# inversor.net
KiCad netlist of a schematic drawn in EAGLE
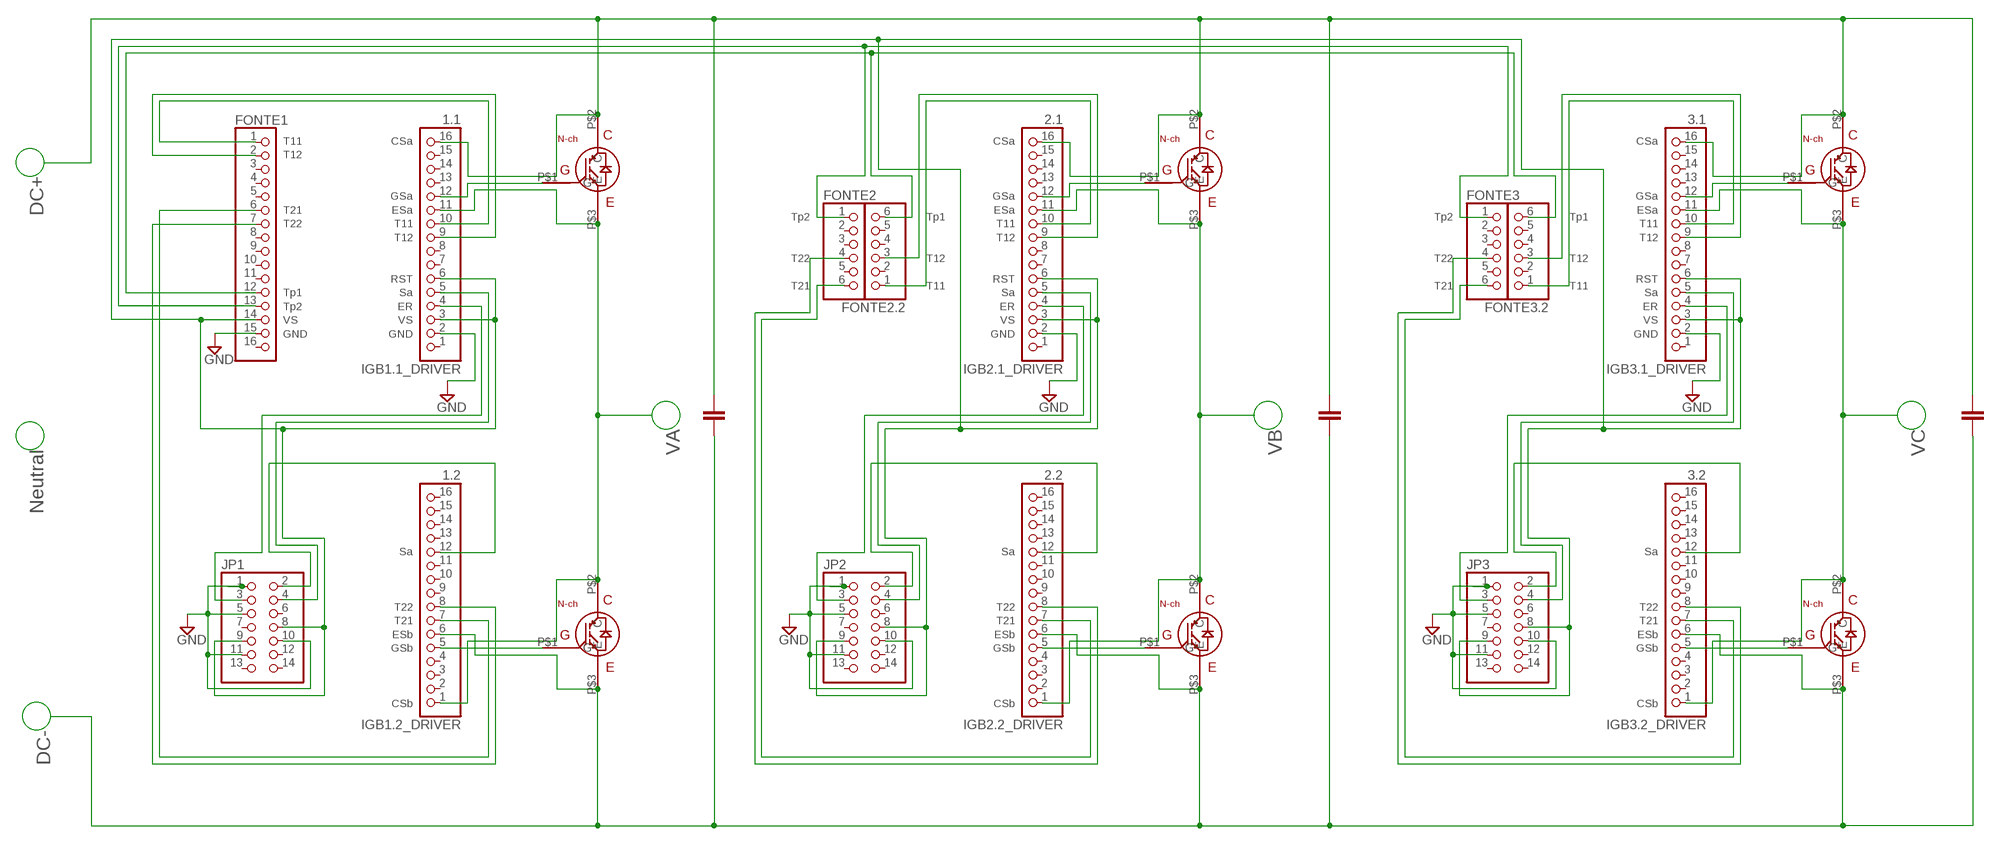
[diagram p0: schematic, sheet 1]

(export (version "E")
  (design (tool "Eeschema 10.0.6"))
  (components
    (comp (ref "FONTE1")
      (value "PINHD-1X16")
      (footprint "eagle-import:1X16")
      (libsource (lib "eagle-import") (part "PINHD-1X16"))
    )
    (comp (ref "FONTE2")
      (value "PINHD-1X6")
      (footprint "eagle-import:1X06")
      (libsource (lib "eagle-import") (part "PINHD-1X6"))
    )
    (comp (ref "FONTE2.2")
      (value "PINHD-1X6")
      (footprint "eagle-import:1X06")
      (libsource (lib "eagle-import") (part "PINHD-1X6"))
    )
    (comp (ref "FONTE3")
      (value "PINHD-1X6")
      (footprint "eagle-import:1X06")
      (libsource (lib "eagle-import") (part "PINHD-1X6"))
    )
    (comp (ref "FONTE3.2")
      (value "PINHD-1X6")
      (footprint "eagle-import:1X06")
      (libsource (lib "eagle-import") (part "PINHD-1X6"))
    )
    (comp (ref "IGB1.1_DRIVER")
      (value "1.1")
      (footprint "eagle-import:1X16")
      (libsource (lib "eagle-import") (part "PINHD-1X16"))
    )
    (comp (ref "IGB1.2_DRIVER")
      (value "1.2")
      (footprint "eagle-import:1X16")
      (libsource (lib "eagle-import") (part "PINHD-1X16"))
    )
    (comp (ref "IGB2.1_DRIVER")
      (value "2.1")
      (footprint "eagle-import:1X16")
      (libsource (lib "eagle-import") (part "PINHD-1X16"))
    )
    (comp (ref "IGB2.2_DRIVER")
      (value "2.2")
      (footprint "eagle-import:1X16")
      (libsource (lib "eagle-import") (part "PINHD-1X16"))
    )
    (comp (ref "IGB3.1_DRIVER")
      (value "3.1")
      (footprint "eagle-import:1X16")
      (libsource (lib "eagle-import") (part "PINHD-1X16"))
    )
    (comp (ref "IGB3.2_DRIVER")
      (value "3.2")
      (footprint "eagle-import:1X16")
      (libsource (lib "eagle-import") (part "PINHD-1X16"))
    )
    (comp (ref "JP1")
      (value "PINHD-2X7")
      (footprint "eagle-import:2X07")
      (libsource (lib "eagle-import") (part "PINHD-2X7"))
    )
    (comp (ref "JP2")
      (value "PINHD-2X7")
      (footprint "eagle-import:2X07")
      (libsource (lib "eagle-import") (part "PINHD-2X7"))
    )
    (comp (ref "JP3")
      (value "PINHD-2X7")
      (footprint "eagle-import:2X07")
      (libsource (lib "eagle-import") (part "PINHD-2X7"))
    )
    (comp (ref "U$1")
      (value "TO-247A")
      (footprint "eagle-import:TO-247")
      (libsource (lib "eagle-import") (part "TO-247A"))
    )
    (comp (ref "U$2")
      (value "TO-247A")
      (footprint "eagle-import:TO-247")
      (libsource (lib "eagle-import") (part "TO-247A"))
    )
    (comp (ref "U$3")
      (value "TO-247A")
      (footprint "eagle-import:TO-247")
      (libsource (lib "eagle-import") (part "TO-247A"))
    )
    (comp (ref "U$4")
      (value "TO-247A")
      (footprint "eagle-import:TO-247")
      (libsource (lib "eagle-import") (part "TO-247A"))
    )
    (comp (ref "U$5")
      (value "TO-247A")
      (footprint "eagle-import:TO-247")
      (libsource (lib "eagle-import") (part "TO-247A"))
    )
    (comp (ref "U$6")
      (value "TO-247A")
      (footprint "eagle-import:TO-247")
      (libsource (lib "eagle-import") (part "TO-247A"))
    )
  )
  (nets
    (net (code "1") (name "GND") (class "Default")
      (node (ref "FONTE1") (pin "15") (pinfunction "15_15") (pintype "passive"))
      (node (ref "IGB1.1_DRIVER") (pin "2") (pinfunction "2_2") (pintype "passive"))
      (node (ref "IGB2.1_DRIVER") (pin "2") (pinfunction "2_2") (pintype "passive"))
      (node (ref "IGB3.1_DRIVER") (pin "2") (pinfunction "2_2") (pintype "passive"))
      (node (ref "JP1") (pin "1") (pinfunction "1_1") (pintype "passive"))
      (node (ref "JP1") (pin "10") (pinfunction "10_10") (pintype "passive"))
      (node (ref "JP1") (pin "11") (pinfunction "11_11") (pintype "passive"))
      (node (ref "JP1") (pin "5") (pinfunction "5_5") (pintype "passive"))
      (node (ref "JP2") (pin "1") (pinfunction "1_1") (pintype "passive"))
      (node (ref "JP2") (pin "10") (pinfunction "10_10") (pintype "passive"))
      (node (ref "JP2") (pin "11") (pinfunction "11_11") (pintype "passive"))
      (node (ref "JP2") (pin "5") (pinfunction "5_5") (pintype "passive"))
      (node (ref "JP3") (pin "1") (pinfunction "1_1") (pintype "passive"))
      (node (ref "JP3") (pin "10") (pinfunction "10_10") (pintype "passive"))
      (node (ref "JP3") (pin "11") (pinfunction "11_11") (pintype "passive"))
      (node (ref "JP3") (pin "5") (pinfunction "5_5") (pintype "passive"))
    )
    (net (code "2") (name "Net-(FONTE1-Pad1)") (class "Default")
      (node (ref "FONTE1") (pin "1") (pinfunction "1_1") (pintype "passive"))
      (node (ref "IGB1.1_DRIVER") (pin "10") (pinfunction "10_10") (pintype "passive"))
    )
    (net (code "3") (name "Net-(FONTE1-Pad2)") (class "Default")
      (node (ref "FONTE1") (pin "2") (pinfunction "2_2") (pintype "passive"))
      (node (ref "IGB1.1_DRIVER") (pin "9") (pinfunction "9_9") (pintype "passive"))
    )
    (net (code "4") (name "Net-(FONTE1-Pad6)") (class "Default")
      (node (ref "FONTE1") (pin "6") (pinfunction "6_6") (pintype "passive"))
      (node (ref "IGB1.2_DRIVER") (pin "7") (pinfunction "7_7") (pintype "passive"))
    )
    (net (code "5") (name "Net-(FONTE1-Pad7)") (class "Default")
      (node (ref "FONTE1") (pin "7") (pinfunction "7_7") (pintype "passive"))
      (node (ref "IGB1.2_DRIVER") (pin "8") (pinfunction "8_8") (pintype "passive"))
    )
    (net (code "6") (name "Net-(FONTE1-Pad12)") (class "Default")
      (node (ref "FONTE1") (pin "12") (pinfunction "12_12") (pintype "passive"))
      (node (ref "FONTE2.2") (pin "6") (pinfunction "6_6") (pintype "passive"))
      (node (ref "FONTE3.2") (pin "6") (pinfunction "6_6") (pintype "passive"))
    )
    (net (code "7") (name "Net-(FONTE1-Pad13)") (class "Default")
      (node (ref "FONTE1") (pin "13") (pinfunction "13_13") (pintype "passive"))
      (node (ref "FONTE2") (pin "1") (pinfunction "1_1") (pintype "passive"))
      (node (ref "FONTE3") (pin "1") (pinfunction "1_1") (pintype "passive"))
    )
    (net (code "8") (name "Net-(FONTE1-Pad14)") (class "Default")
      (node (ref "FONTE1") (pin "14") (pinfunction "14_14") (pintype "passive"))
      (node (ref "IGB1.1_DRIVER") (pin "3") (pinfunction "3_3") (pintype "passive"))
      (node (ref "IGB1.1_DRIVER") (pin "6") (pinfunction "6_6") (pintype "passive"))
      (node (ref "IGB2.1_DRIVER") (pin "3") (pinfunction "3_3") (pintype "passive"))
      (node (ref "IGB2.1_DRIVER") (pin "6") (pinfunction "6_6") (pintype "passive"))
      (node (ref "IGB3.1_DRIVER") (pin "3") (pinfunction "3_3") (pintype "passive"))
      (node (ref "IGB3.1_DRIVER") (pin "6") (pinfunction "6_6") (pintype "passive"))
      (node (ref "JP1") (pin "8") (pinfunction "8_8") (pintype "passive"))
      (node (ref "JP1") (pin "9") (pinfunction "9_9") (pintype "passive"))
      (node (ref "JP2") (pin "8") (pinfunction "8_8") (pintype "passive"))
      (node (ref "JP2") (pin "9") (pinfunction "9_9") (pintype "passive"))
      (node (ref "JP3") (pin "8") (pinfunction "8_8") (pintype "passive"))
      (node (ref "JP3") (pin "9") (pinfunction "9_9") (pintype "passive"))
    )
    (net (code "9") (name "Net-(FONTE2-Pad4)") (class "Default")
      (node (ref "FONTE2") (pin "4") (pinfunction "4_4") (pintype "passive"))
      (node (ref "IGB2.2_DRIVER") (pin "8") (pinfunction "8_8") (pintype "passive"))
    )
    (net (code "10") (name "Net-(FONTE2-Pad6)") (class "Default")
      (node (ref "FONTE2") (pin "6") (pinfunction "6_6") (pintype "passive"))
      (node (ref "IGB2.2_DRIVER") (pin "7") (pinfunction "7_7") (pintype "passive"))
    )
    (net (code "11") (name "Net-(FONTE2.2-Pad1)") (class "Default")
      (node (ref "FONTE2.2") (pin "1") (pinfunction "1_1") (pintype "passive"))
      (node (ref "IGB2.1_DRIVER") (pin "10") (pinfunction "10_10") (pintype "passive"))
    )
    (net (code "12") (name "Net-(FONTE2.2-Pad3)") (class "Default")
      (node (ref "FONTE2.2") (pin "3") (pinfunction "3_3") (pintype "passive"))
      (node (ref "IGB2.1_DRIVER") (pin "9") (pinfunction "9_9") (pintype "passive"))
    )
    (net (code "13") (name "Net-(FONTE3-Pad4)") (class "Default")
      (node (ref "FONTE3") (pin "4") (pinfunction "4_4") (pintype "passive"))
      (node (ref "IGB3.2_DRIVER") (pin "8") (pinfunction "8_8") (pintype "passive"))
    )
    (net (code "14") (name "Net-(FONTE3-Pad6)") (class "Default")
      (node (ref "FONTE3") (pin "6") (pinfunction "6_6") (pintype "passive"))
      (node (ref "IGB3.2_DRIVER") (pin "7") (pinfunction "7_7") (pintype "passive"))
    )
    (net (code "15") (name "Net-(FONTE3.2-Pad1)") (class "Default")
      (node (ref "FONTE3.2") (pin "1") (pinfunction "1_1") (pintype "passive"))
      (node (ref "IGB3.1_DRIVER") (pin "10") (pinfunction "10_10") (pintype "passive"))
    )
    (net (code "16") (name "Net-(FONTE3.2-Pad3)") (class "Default")
      (node (ref "FONTE3.2") (pin "3") (pinfunction "3_3") (pintype "passive"))
      (node (ref "IGB3.1_DRIVER") (pin "9") (pinfunction "9_9") (pintype "passive"))
    )
    (net (code "17") (name "Net-(IGB1.1_DRIVER-Pad4)") (class "Default")
      (node (ref "IGB1.1_DRIVER") (pin "4") (pinfunction "4_4") (pintype "passive"))
      (node (ref "JP1") (pin "3") (pinfunction "3_3") (pintype "passive"))
    )
    (net (code "18") (name "Net-(IGB1.1_DRIVER-Pad5)") (class "Default")
      (node (ref "IGB1.1_DRIVER") (pin "5") (pinfunction "5_5") (pintype "passive"))
      (node (ref "JP1") (pin "4") (pinfunction "4_4") (pintype "passive"))
    )
    (net (code "19") (name "Net-(IGB1.2_DRIVER-Pad12)") (class "Default")
      (node (ref "IGB1.2_DRIVER") (pin "12") (pinfunction "12_12") (pintype "passive"))
      (node (ref "JP1") (pin "2") (pinfunction "2_2") (pintype "passive"))
    )
    (net (code "20") (name "Net-(IGB2.1_DRIVER-Pad4)") (class "Default")
      (node (ref "IGB2.1_DRIVER") (pin "4") (pinfunction "4_4") (pintype "passive"))
      (node (ref "JP2") (pin "3") (pinfunction "3_3") (pintype "passive"))
    )
    (net (code "21") (name "Net-(IGB2.1_DRIVER-Pad5)") (class "Default")
      (node (ref "IGB2.1_DRIVER") (pin "5") (pinfunction "5_5") (pintype "passive"))
      (node (ref "JP2") (pin "4") (pinfunction "4_4") (pintype "passive"))
    )
    (net (code "22") (name "Net-(IGB2.2_DRIVER-Pad12)") (class "Default")
      (node (ref "IGB2.2_DRIVER") (pin "12") (pinfunction "12_12") (pintype "passive"))
      (node (ref "JP2") (pin "2") (pinfunction "2_2") (pintype "passive"))
    )
    (net (code "23") (name "Net-(IGB3.1_DRIVER-Pad4)") (class "Default")
      (node (ref "IGB3.1_DRIVER") (pin "4") (pinfunction "4_4") (pintype "passive"))
      (node (ref "JP3") (pin "3") (pinfunction "3_3") (pintype "passive"))
    )
    (net (code "24") (name "Net-(IGB3.1_DRIVER-Pad5)") (class "Default")
      (node (ref "IGB3.1_DRIVER") (pin "5") (pinfunction "5_5") (pintype "passive"))
      (node (ref "JP3") (pin "4") (pinfunction "4_4") (pintype "passive"))
    )
    (net (code "25") (name "Net-(IGB3.2_DRIVER-Pad12)") (class "Default")
      (node (ref "IGB3.2_DRIVER") (pin "12") (pinfunction "12_12") (pintype "passive"))
      (node (ref "JP3") (pin "2") (pinfunction "2_2") (pintype "passive"))
    )
    (net (code "26") (name "Net-(U$1-C)") (class "Default")
      (node (ref "IGB1.1_DRIVER") (pin "16") (pinfunction "16_16") (pintype "passive"))
      (node (ref "IGB2.1_DRIVER") (pin "16") (pinfunction "16_16") (pintype "passive"))
      (node (ref "IGB3.1_DRIVER") (pin "16") (pinfunction "16_16") (pintype "passive"))
      (node (ref "U$1") (pin "P$2") (pinfunction "C_P$2") (pintype "bidirectional"))
      (node (ref "U$3") (pin "P$2") (pinfunction "C_P$2") (pintype "bidirectional"))
      (node (ref "U$5") (pin "P$2") (pinfunction "C_P$2") (pintype "bidirectional"))
    )
    (net (code "27") (name "Net-(U$1-E)") (class "Default")
      (node (ref "IGB1.1_DRIVER") (pin "11") (pinfunction "11_11") (pintype "passive"))
      (node (ref "IGB1.2_DRIVER") (pin "1") (pinfunction "1_1") (pintype "passive"))
      (node (ref "U$1") (pin "P$3") (pinfunction "E_P$3") (pintype "bidirectional"))
      (node (ref "U$2") (pin "P$2") (pinfunction "C_P$2") (pintype "bidirectional"))
    )
    (net (code "28") (name "Net-(U$1-G)") (class "Default")
      (node (ref "IGB1.1_DRIVER") (pin "12") (pinfunction "12_12") (pintype "passive"))
      (node (ref "U$1") (pin "P$1") (pinfunction "G_P$1") (pintype "bidirectional"))
    )
    (net (code "29") (name "Net-(U$2-E)") (class "Default")
      (node (ref "IGB1.2_DRIVER") (pin "6") (pinfunction "6_6") (pintype "passive"))
      (node (ref "IGB2.2_DRIVER") (pin "6") (pinfunction "6_6") (pintype "passive"))
      (node (ref "IGB3.2_DRIVER") (pin "6") (pinfunction "6_6") (pintype "passive"))
      (node (ref "U$2") (pin "P$3") (pinfunction "E_P$3") (pintype "bidirectional"))
      (node (ref "U$4") (pin "P$3") (pinfunction "E_P$3") (pintype "bidirectional"))
      (node (ref "U$6") (pin "P$3") (pinfunction "E_P$3") (pintype "bidirectional"))
    )
    (net (code "30") (name "Net-(U$2-G)") (class "Default")
      (node (ref "IGB1.2_DRIVER") (pin "5") (pinfunction "5_5") (pintype "passive"))
      (node (ref "U$2") (pin "P$1") (pinfunction "G_P$1") (pintype "bidirectional"))
    )
    (net (code "31") (name "Net-(U$3-E)") (class "Default")
      (node (ref "IGB2.1_DRIVER") (pin "11") (pinfunction "11_11") (pintype "passive"))
      (node (ref "IGB2.2_DRIVER") (pin "1") (pinfunction "1_1") (pintype "passive"))
      (node (ref "U$3") (pin "P$3") (pinfunction "E_P$3") (pintype "bidirectional"))
      (node (ref "U$4") (pin "P$2") (pinfunction "C_P$2") (pintype "bidirectional"))
    )
    (net (code "32") (name "Net-(U$3-G)") (class "Default")
      (node (ref "IGB2.1_DRIVER") (pin "12") (pinfunction "12_12") (pintype "passive"))
      (node (ref "U$3") (pin "P$1") (pinfunction "G_P$1") (pintype "bidirectional"))
    )
    (net (code "33") (name "Net-(U$4-G)") (class "Default")
      (node (ref "IGB2.2_DRIVER") (pin "5") (pinfunction "5_5") (pintype "passive"))
      (node (ref "U$4") (pin "P$1") (pinfunction "G_P$1") (pintype "bidirectional"))
    )
    (net (code "34") (name "Net-(U$5-E)") (class "Default")
      (node (ref "IGB3.1_DRIVER") (pin "11") (pinfunction "11_11") (pintype "passive"))
      (node (ref "IGB3.2_DRIVER") (pin "1") (pinfunction "1_1") (pintype "passive"))
      (node (ref "U$5") (pin "P$3") (pinfunction "E_P$3") (pintype "bidirectional"))
      (node (ref "U$6") (pin "P$2") (pinfunction "C_P$2") (pintype "bidirectional"))
    )
    (net (code "35") (name "Net-(U$5-G)") (class "Default")
      (node (ref "IGB3.1_DRIVER") (pin "12") (pinfunction "12_12") (pintype "passive"))
      (node (ref "U$5") (pin "P$1") (pinfunction "G_P$1") (pintype "bidirectional"))
    )
    (net (code "36") (name "Net-(U$6-G)") (class "Default")
      (node (ref "IGB3.2_DRIVER") (pin "5") (pinfunction "5_5") (pintype "passive"))
      (node (ref "U$6") (pin "P$1") (pinfunction "G_P$1") (pintype "bidirectional"))
    )
    (net (code "37") (name "unconnected-(FONTE1-Pad3)") (class "Default")
      (node (ref "FONTE1") (pin "3") (pinfunction "3_3") (pintype "passive"))
    )
    (net (code "38") (name "unconnected-(FONTE1-Pad4)") (class "Default")
      (node (ref "FONTE1") (pin "4") (pinfunction "4_4") (pintype "passive"))
    )
    (net (code "39") (name "unconnected-(FONTE1-Pad5)") (class "Default")
      (node (ref "FONTE1") (pin "5") (pinfunction "5_5") (pintype "passive"))
    )
    (net (code "40") (name "unconnected-(FONTE1-Pad8)") (class "Default")
      (node (ref "FONTE1") (pin "8") (pinfunction "8_8") (pintype "passive"))
    )
    (net (code "41") (name "unconnected-(FONTE1-Pad9)") (class "Default")
      (node (ref "FONTE1") (pin "9") (pinfunction "9_9") (pintype "passive"))
    )
    (net (code "42") (name "unconnected-(FONTE1-Pad10)") (class "Default")
      (node (ref "FONTE1") (pin "10") (pinfunction "10_10") (pintype "passive"))
    )
    (net (code "43") (name "unconnected-(FONTE1-Pad11)") (class "Default")
      (node (ref "FONTE1") (pin "11") (pinfunction "11_11") (pintype "passive"))
    )
    (net (code "44") (name "unconnected-(FONTE1-Pad16)") (class "Default")
      (node (ref "FONTE1") (pin "16") (pinfunction "16_16") (pintype "passive"))
    )
    (net (code "45") (name "unconnected-(FONTE2-Pad2)") (class "Default")
      (node (ref "FONTE2") (pin "2") (pinfunction "2_2") (pintype "passive"))
    )
    (net (code "46") (name "unconnected-(FONTE2-Pad3)") (class "Default")
      (node (ref "FONTE2") (pin "3") (pinfunction "3_3") (pintype "passive"))
    )
    (net (code "47") (name "unconnected-(FONTE2-Pad5)") (class "Default")
      (node (ref "FONTE2") (pin "5") (pinfunction "5_5") (pintype "passive"))
    )
    (net (code "48") (name "unconnected-(FONTE2.2-Pad2)") (class "Default")
      (node (ref "FONTE2.2") (pin "2") (pinfunction "2_2") (pintype "passive"))
    )
    (net (code "49") (name "unconnected-(FONTE2.2-Pad4)") (class "Default")
      (node (ref "FONTE2.2") (pin "4") (pinfunction "4_4") (pintype "passive"))
    )
    (net (code "50") (name "unconnected-(FONTE2.2-Pad5)") (class "Default")
      (node (ref "FONTE2.2") (pin "5") (pinfunction "5_5") (pintype "passive"))
    )
    (net (code "51") (name "unconnected-(FONTE3-Pad2)") (class "Default")
      (node (ref "FONTE3") (pin "2") (pinfunction "2_2") (pintype "passive"))
    )
    (net (code "52") (name "unconnected-(FONTE3-Pad3)") (class "Default")
      (node (ref "FONTE3") (pin "3") (pinfunction "3_3") (pintype "passive"))
    )
    (net (code "53") (name "unconnected-(FONTE3-Pad5)") (class "Default")
      (node (ref "FONTE3") (pin "5") (pinfunction "5_5") (pintype "passive"))
    )
    (net (code "54") (name "unconnected-(FONTE3.2-Pad2)") (class "Default")
      (node (ref "FONTE3.2") (pin "2") (pinfunction "2_2") (pintype "passive"))
    )
    (net (code "55") (name "unconnected-(FONTE3.2-Pad4)") (class "Default")
      (node (ref "FONTE3.2") (pin "4") (pinfunction "4_4") (pintype "passive"))
    )
    (net (code "56") (name "unconnected-(FONTE3.2-Pad5)") (class "Default")
      (node (ref "FONTE3.2") (pin "5") (pinfunction "5_5") (pintype "passive"))
    )
    (net (code "57") (name "unconnected-(IGB1.1_DRIVER-Pad1)") (class "Default")
      (node (ref "IGB1.1_DRIVER") (pin "1") (pinfunction "1_1") (pintype "passive"))
    )
    (net (code "58") (name "unconnected-(IGB1.1_DRIVER-Pad7)") (class "Default")
      (node (ref "IGB1.1_DRIVER") (pin "7") (pinfunction "7_7") (pintype "passive"))
    )
    (net (code "59") (name "unconnected-(IGB1.1_DRIVER-Pad8)") (class "Default")
      (node (ref "IGB1.1_DRIVER") (pin "8") (pinfunction "8_8") (pintype "passive"))
    )
    (net (code "60") (name "unconnected-(IGB1.1_DRIVER-Pad13)") (class "Default")
      (node (ref "IGB1.1_DRIVER") (pin "13") (pinfunction "13_13") (pintype "passive"))
    )
    (net (code "61") (name "unconnected-(IGB1.1_DRIVER-Pad14)") (class "Default")
      (node (ref "IGB1.1_DRIVER") (pin "14") (pinfunction "14_14") (pintype "passive"))
    )
    (net (code "62") (name "unconnected-(IGB1.1_DRIVER-Pad15)") (class "Default")
      (node (ref "IGB1.1_DRIVER") (pin "15") (pinfunction "15_15") (pintype "passive"))
    )
    (net (code "63") (name "unconnected-(IGB1.2_DRIVER-Pad2)") (class "Default")
      (node (ref "IGB1.2_DRIVER") (pin "2") (pinfunction "2_2") (pintype "passive"))
    )
    (net (code "64") (name "unconnected-(IGB1.2_DRIVER-Pad3)") (class "Default")
      (node (ref "IGB1.2_DRIVER") (pin "3") (pinfunction "3_3") (pintype "passive"))
    )
    (net (code "65") (name "unconnected-(IGB1.2_DRIVER-Pad4)") (class "Default")
      (node (ref "IGB1.2_DRIVER") (pin "4") (pinfunction "4_4") (pintype "passive"))
    )
    (net (code "66") (name "unconnected-(IGB1.2_DRIVER-Pad9)") (class "Default")
      (node (ref "IGB1.2_DRIVER") (pin "9") (pinfunction "9_9") (pintype "passive"))
    )
    (net (code "67") (name "unconnected-(IGB1.2_DRIVER-Pad10)") (class "Default")
      (node (ref "IGB1.2_DRIVER") (pin "10") (pinfunction "10_10") (pintype "passive"))
    )
    (net (code "68") (name "unconnected-(IGB1.2_DRIVER-Pad11)") (class "Default")
      (node (ref "IGB1.2_DRIVER") (pin "11") (pinfunction "11_11") (pintype "passive"))
    )
    (net (code "69") (name "unconnected-(IGB1.2_DRIVER-Pad13)") (class "Default")
      (node (ref "IGB1.2_DRIVER") (pin "13") (pinfunction "13_13") (pintype "passive"))
    )
    (net (code "70") (name "unconnected-(IGB1.2_DRIVER-Pad14)") (class "Default")
      (node (ref "IGB1.2_DRIVER") (pin "14") (pinfunction "14_14") (pintype "passive"))
    )
    (net (code "71") (name "unconnected-(IGB1.2_DRIVER-Pad15)") (class "Default")
      (node (ref "IGB1.2_DRIVER") (pin "15") (pinfunction "15_15") (pintype "passive"))
    )
    (net (code "72") (name "unconnected-(IGB1.2_DRIVER-Pad16)") (class "Default")
      (node (ref "IGB1.2_DRIVER") (pin "16") (pinfunction "16_16") (pintype "passive"))
    )
    (net (code "73") (name "unconnected-(IGB2.1_DRIVER-Pad1)") (class "Default")
      (node (ref "IGB2.1_DRIVER") (pin "1") (pinfunction "1_1") (pintype "passive"))
    )
    (net (code "74") (name "unconnected-(IGB2.1_DRIVER-Pad7)") (class "Default")
      (node (ref "IGB2.1_DRIVER") (pin "7") (pinfunction "7_7") (pintype "passive"))
    )
    (net (code "75") (name "unconnected-(IGB2.1_DRIVER-Pad8)") (class "Default")
      (node (ref "IGB2.1_DRIVER") (pin "8") (pinfunction "8_8") (pintype "passive"))
    )
    (net (code "76") (name "unconnected-(IGB2.1_DRIVER-Pad13)") (class "Default")
      (node (ref "IGB2.1_DRIVER") (pin "13") (pinfunction "13_13") (pintype "passive"))
    )
    (net (code "77") (name "unconnected-(IGB2.1_DRIVER-Pad14)") (class "Default")
      (node (ref "IGB2.1_DRIVER") (pin "14") (pinfunction "14_14") (pintype "passive"))
    )
    (net (code "78") (name "unconnected-(IGB2.1_DRIVER-Pad15)") (class "Default")
      (node (ref "IGB2.1_DRIVER") (pin "15") (pinfunction "15_15") (pintype "passive"))
    )
    (net (code "79") (name "unconnected-(IGB2.2_DRIVER-Pad2)") (class "Default")
      (node (ref "IGB2.2_DRIVER") (pin "2") (pinfunction "2_2") (pintype "passive"))
    )
    (net (code "80") (name "unconnected-(IGB2.2_DRIVER-Pad3)") (class "Default")
      (node (ref "IGB2.2_DRIVER") (pin "3") (pinfunction "3_3") (pintype "passive"))
    )
    (net (code "81") (name "unconnected-(IGB2.2_DRIVER-Pad4)") (class "Default")
      (node (ref "IGB2.2_DRIVER") (pin "4") (pinfunction "4_4") (pintype "passive"))
    )
    (net (code "82") (name "unconnected-(IGB2.2_DRIVER-Pad9)") (class "Default")
      (node (ref "IGB2.2_DRIVER") (pin "9") (pinfunction "9_9") (pintype "passive"))
    )
    (net (code "83") (name "unconnected-(IGB2.2_DRIVER-Pad10)") (class "Default")
      (node (ref "IGB2.2_DRIVER") (pin "10") (pinfunction "10_10") (pintype "passive"))
    )
    (net (code "84") (name "unconnected-(IGB2.2_DRIVER-Pad11)") (class "Default")
      (node (ref "IGB2.2_DRIVER") (pin "11") (pinfunction "11_11") (pintype "passive"))
    )
    (net (code "85") (name "unconnected-(IGB2.2_DRIVER-Pad13)") (class "Default")
      (node (ref "IGB2.2_DRIVER") (pin "13") (pinfunction "13_13") (pintype "passive"))
    )
    (net (code "86") (name "unconnected-(IGB2.2_DRIVER-Pad14)") (class "Default")
      (node (ref "IGB2.2_DRIVER") (pin "14") (pinfunction "14_14") (pintype "passive"))
    )
    (net (code "87") (name "unconnected-(IGB2.2_DRIVER-Pad15)") (class "Default")
      (node (ref "IGB2.2_DRIVER") (pin "15") (pinfunction "15_15") (pintype "passive"))
    )
    (net (code "88") (name "unconnected-(IGB2.2_DRIVER-Pad16)") (class "Default")
      (node (ref "IGB2.2_DRIVER") (pin "16") (pinfunction "16_16") (pintype "passive"))
    )
    (net (code "89") (name "unconnected-(IGB3.1_DRIVER-Pad1)") (class "Default")
      (node (ref "IGB3.1_DRIVER") (pin "1") (pinfunction "1_1") (pintype "passive"))
    )
    (net (code "90") (name "unconnected-(IGB3.1_DRIVER-Pad7)") (class "Default")
      (node (ref "IGB3.1_DRIVER") (pin "7") (pinfunction "7_7") (pintype "passive"))
    )
    (net (code "91") (name "unconnected-(IGB3.1_DRIVER-Pad8)") (class "Default")
      (node (ref "IGB3.1_DRIVER") (pin "8") (pinfunction "8_8") (pintype "passive"))
    )
    (net (code "92") (name "unconnected-(IGB3.1_DRIVER-Pad13)") (class "Default")
      (node (ref "IGB3.1_DRIVER") (pin "13") (pinfunction "13_13") (pintype "passive"))
    )
    (net (code "93") (name "unconnected-(IGB3.1_DRIVER-Pad14)") (class "Default")
      (node (ref "IGB3.1_DRIVER") (pin "14") (pinfunction "14_14") (pintype "passive"))
    )
    (net (code "94") (name "unconnected-(IGB3.1_DRIVER-Pad15)") (class "Default")
      (node (ref "IGB3.1_DRIVER") (pin "15") (pinfunction "15_15") (pintype "passive"))
    )
    (net (code "95") (name "unconnected-(IGB3.2_DRIVER-Pad2)") (class "Default")
      (node (ref "IGB3.2_DRIVER") (pin "2") (pinfunction "2_2") (pintype "passive"))
    )
    (net (code "96") (name "unconnected-(IGB3.2_DRIVER-Pad3)") (class "Default")
      (node (ref "IGB3.2_DRIVER") (pin "3") (pinfunction "3_3") (pintype "passive"))
    )
    (net (code "97") (name "unconnected-(IGB3.2_DRIVER-Pad4)") (class "Default")
      (node (ref "IGB3.2_DRIVER") (pin "4") (pinfunction "4_4") (pintype "passive"))
    )
    (net (code "98") (name "unconnected-(IGB3.2_DRIVER-Pad9)") (class "Default")
      (node (ref "IGB3.2_DRIVER") (pin "9") (pinfunction "9_9") (pintype "passive"))
    )
    (net (code "99") (name "unconnected-(IGB3.2_DRIVER-Pad10)") (class "Default")
      (node (ref "IGB3.2_DRIVER") (pin "10") (pinfunction "10_10") (pintype "passive"))
    )
    (net (code "100") (name "unconnected-(IGB3.2_DRIVER-Pad11)") (class "Default")
      (node (ref "IGB3.2_DRIVER") (pin "11") (pinfunction "11_11") (pintype "passive"))
    )
    (net (code "101") (name "unconnected-(IGB3.2_DRIVER-Pad13)") (class "Default")
      (node (ref "IGB3.2_DRIVER") (pin "13") (pinfunction "13_13") (pintype "passive"))
    )
    (net (code "102") (name "unconnected-(IGB3.2_DRIVER-Pad14)") (class "Default")
      (node (ref "IGB3.2_DRIVER") (pin "14") (pinfunction "14_14") (pintype "passive"))
    )
    (net (code "103") (name "unconnected-(IGB3.2_DRIVER-Pad15)") (class "Default")
      (node (ref "IGB3.2_DRIVER") (pin "15") (pinfunction "15_15") (pintype "passive"))
    )
    (net (code "104") (name "unconnected-(IGB3.2_DRIVER-Pad16)") (class "Default")
      (node (ref "IGB3.2_DRIVER") (pin "16") (pinfunction "16_16") (pintype "passive"))
    )
    (net (code "105") (name "unconnected-(JP1-Pad6)") (class "Default")
      (node (ref "JP1") (pin "6") (pinfunction "6_6") (pintype "passive"))
    )
    (net (code "106") (name "unconnected-(JP1-Pad7)") (class "Default")
      (node (ref "JP1") (pin "7") (pinfunction "7_7") (pintype "passive"))
    )
    (net (code "107") (name "unconnected-(JP1-Pad12)") (class "Default")
      (node (ref "JP1") (pin "12") (pinfunction "12_12") (pintype "passive"))
    )
    (net (code "108") (name "unconnected-(JP1-Pad13)") (class "Default")
      (node (ref "JP1") (pin "13") (pinfunction "13_13") (pintype "passive"))
    )
    (net (code "109") (name "unconnected-(JP1-Pad14)") (class "Default")
      (node (ref "JP1") (pin "14") (pinfunction "14_14") (pintype "passive"))
    )
    (net (code "110") (name "unconnected-(JP2-Pad6)") (class "Default")
      (node (ref "JP2") (pin "6") (pinfunction "6_6") (pintype "passive"))
    )
    (net (code "111") (name "unconnected-(JP2-Pad7)") (class "Default")
      (node (ref "JP2") (pin "7") (pinfunction "7_7") (pintype "passive"))
    )
    (net (code "112") (name "unconnected-(JP2-Pad12)") (class "Default")
      (node (ref "JP2") (pin "12") (pinfunction "12_12") (pintype "passive"))
    )
    (net (code "113") (name "unconnected-(JP2-Pad13)") (class "Default")
      (node (ref "JP2") (pin "13") (pinfunction "13_13") (pintype "passive"))
    )
    (net (code "114") (name "unconnected-(JP2-Pad14)") (class "Default")
      (node (ref "JP2") (pin "14") (pinfunction "14_14") (pintype "passive"))
    )
    (net (code "115") (name "unconnected-(JP3-Pad6)") (class "Default")
      (node (ref "JP3") (pin "6") (pinfunction "6_6") (pintype "passive"))
    )
    (net (code "116") (name "unconnected-(JP3-Pad7)") (class "Default")
      (node (ref "JP3") (pin "7") (pinfunction "7_7") (pintype "passive"))
    )
    (net (code "117") (name "unconnected-(JP3-Pad12)") (class "Default")
      (node (ref "JP3") (pin "12") (pinfunction "12_12") (pintype "passive"))
    )
    (net (code "118") (name "unconnected-(JP3-Pad13)") (class "Default")
      (node (ref "JP3") (pin "13") (pinfunction "13_13") (pintype "passive"))
    )
    (net (code "119") (name "unconnected-(JP3-Pad14)") (class "Default")
      (node (ref "JP3") (pin "14") (pinfunction "14_14") (pintype "passive"))
    )
  )
)
